# BW1092_TopLevel.net
KiCad netlist of a schematic drawn in Altium Designer
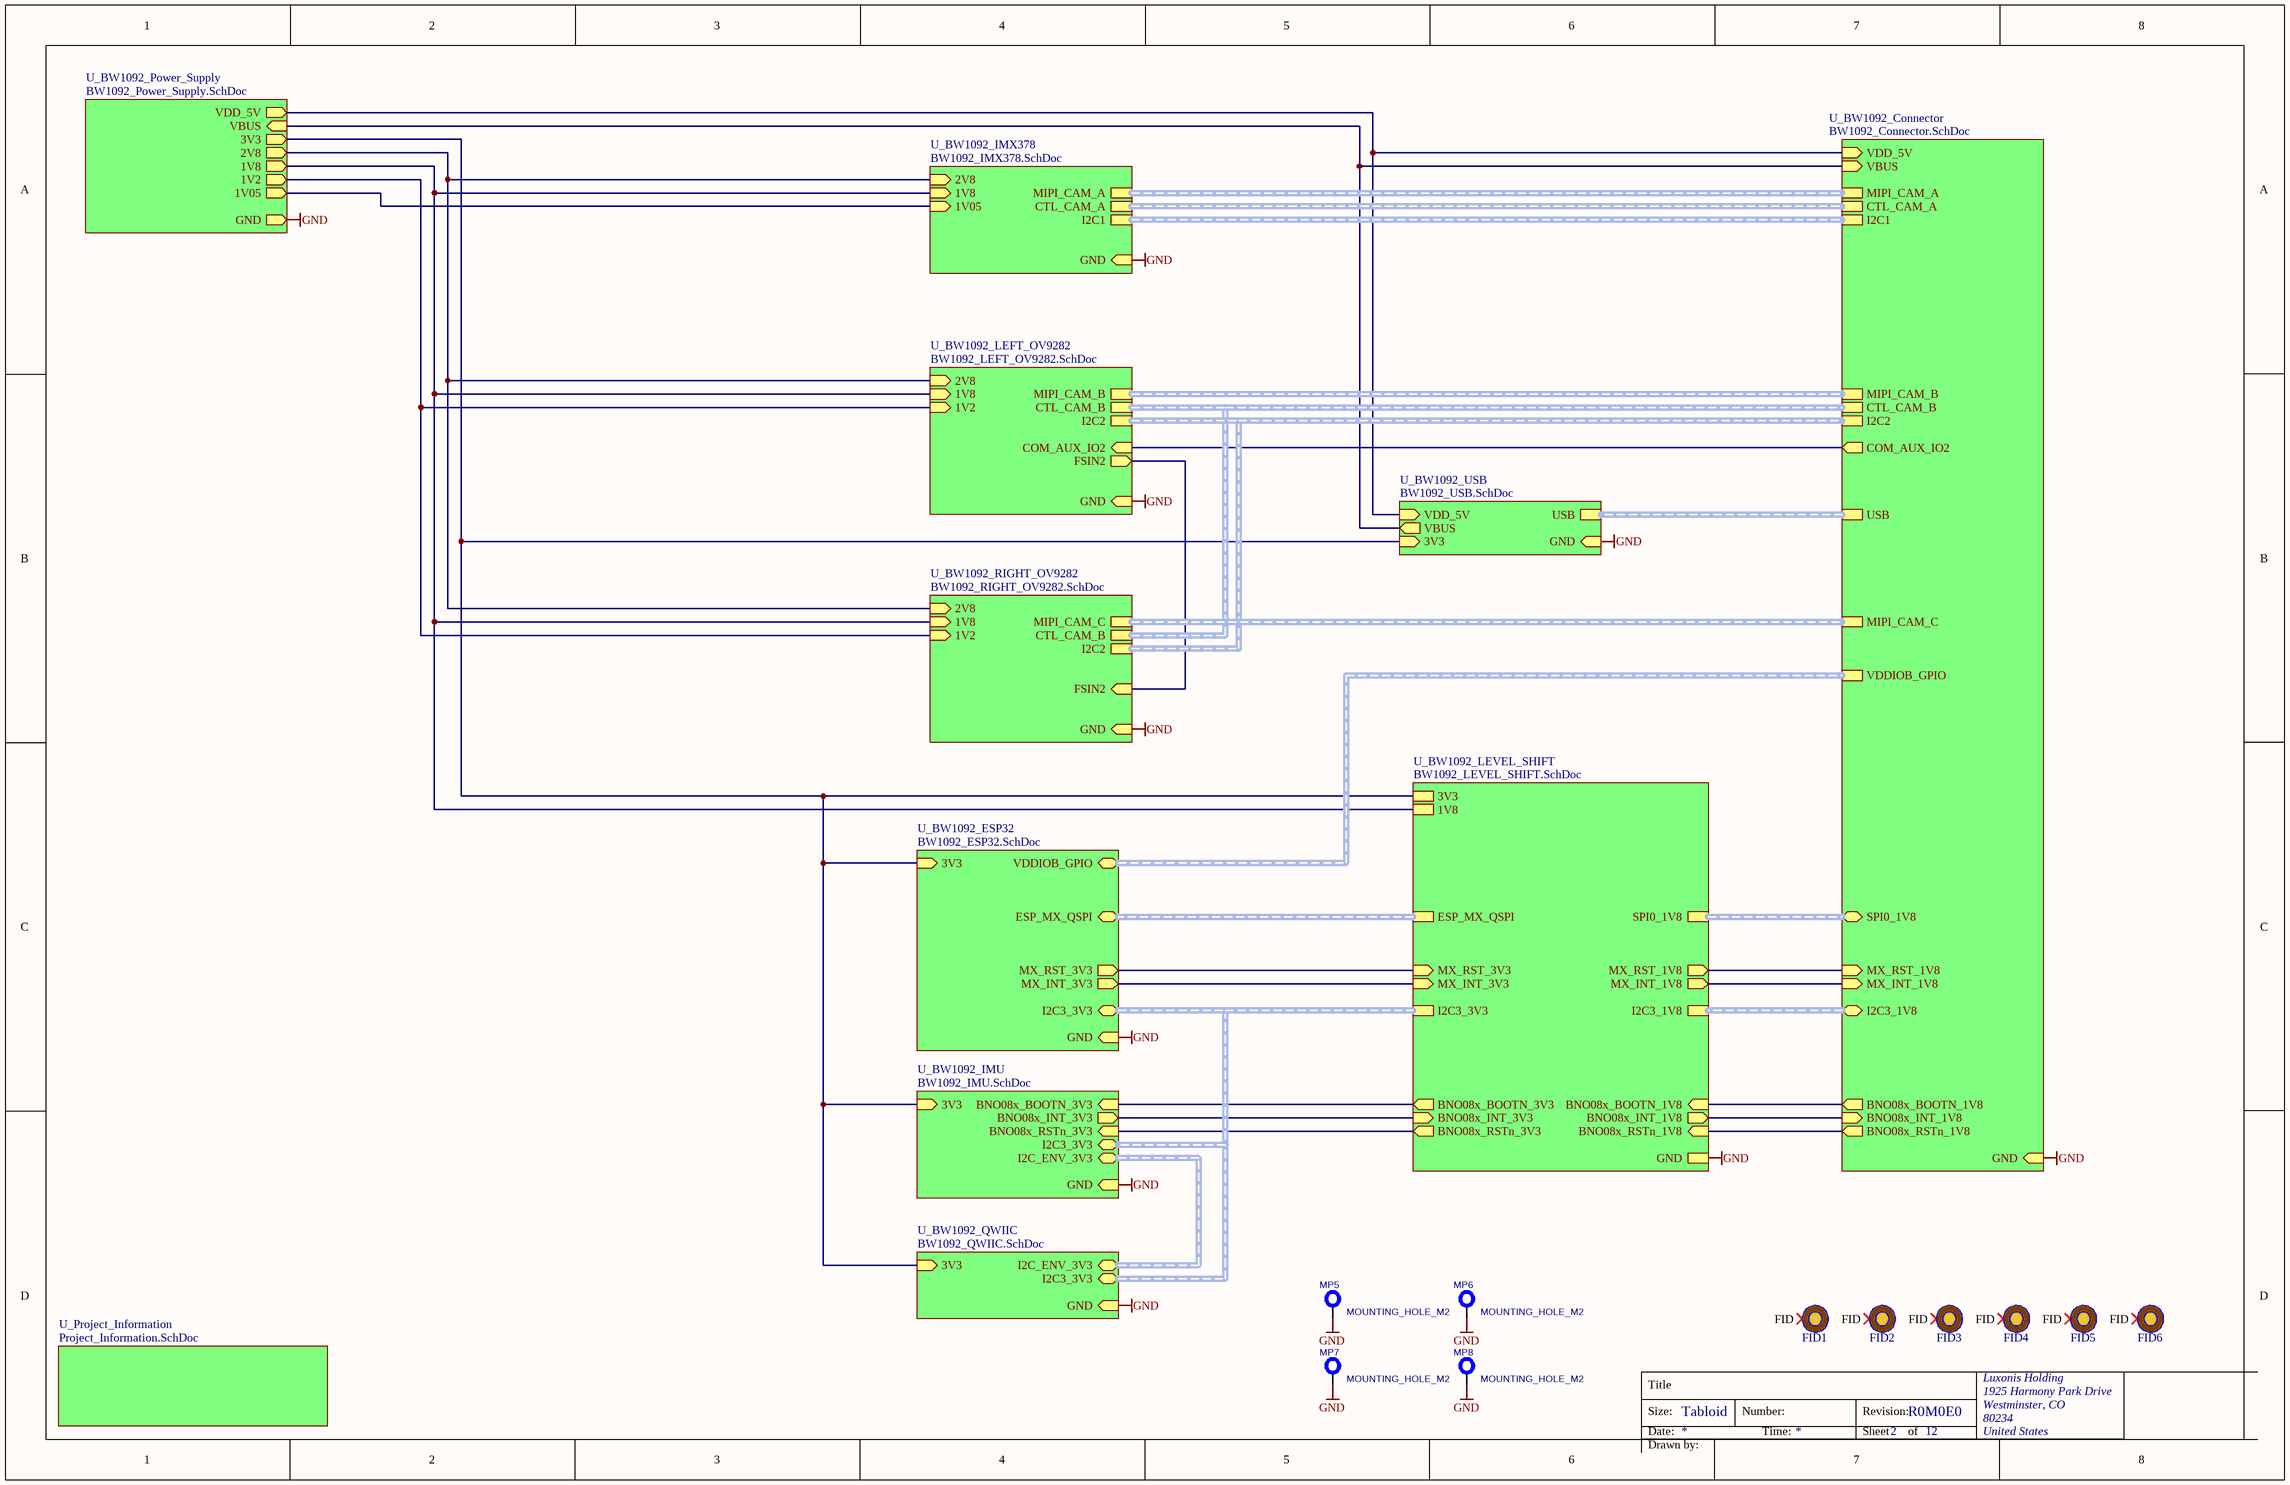
[diagram p0: BW1092_TopLevel.SchDoc]

(export (version "E")
  (design (tool "Eeschema 10.0.6"))
  (components
    (comp (ref "FID1")
      (value "FIDUCIAL_ROUND_1MM")
      (footprint "LuxonisMaster:FIDUCIAL_ROUND_1MM")
      (description "Fiducial with various available footprints")
      (libsource (lib "LuxonisMaster") (part "FIDUCIAL"))
    )
    (comp (ref "FID2")
      (value "FIDUCIAL_ROUND_1MM")
      (footprint "LuxonisMaster:FIDUCIAL_ROUND_1MM")
      (description "Fiducial with various available footprints")
      (libsource (lib "LuxonisMaster") (part "FIDUCIAL"))
    )
    (comp (ref "FID3")
      (value "FIDUCIAL_ROUND_1MM")
      (footprint "LuxonisMaster:FIDUCIAL_ROUND_1MM")
      (description "Fiducial with various available footprints")
      (libsource (lib "LuxonisMaster") (part "FIDUCIAL"))
    )
    (comp (ref "FID4")
      (value "FIDUCIAL_ROUND_1MM")
      (footprint "LuxonisMaster:FIDUCIAL_ROUND_1MM")
      (description "Fiducial with various available footprints")
      (libsource (lib "LuxonisMaster") (part "FIDUCIAL"))
    )
    (comp (ref "FID5")
      (value "FIDUCIAL_ROUND_1MM")
      (footprint "LuxonisMaster:FIDUCIAL_ROUND_1MM")
      (description "Fiducial with various available footprints")
      (libsource (lib "LuxonisMaster") (part "FIDUCIAL"))
    )
    (comp (ref "FID6")
      (value "FIDUCIAL_ROUND_1MM")
      (footprint "LuxonisMaster:FIDUCIAL_ROUND_1MM")
      (description "Fiducial with various available footprints")
      (libsource (lib "LuxonisMaster") (part "FIDUCIAL"))
    )
    (comp (ref "MP5")
      (value "MOUNTING_HOLE_M2")
      (footprint "LuxonisMaster:MOUNTING_HOLE_M2")
      (description "=CurrentFootprint")
      (libsource (lib "LuxonisMaster") (part "MP_Mounting-Holes"))
    )
    (comp (ref "MP6")
      (value "MOUNTING_HOLE_M2")
      (footprint "LuxonisMaster:MOUNTING_HOLE_M2")
      (description "=CurrentFootprint")
      (libsource (lib "LuxonisMaster") (part "MP_Mounting-Holes"))
    )
    (comp (ref "MP7")
      (value "MOUNTING_HOLE_M2")
      (footprint "LuxonisMaster:MOUNTING_HOLE_M2")
      (description "=CurrentFootprint")
      (libsource (lib "LuxonisMaster") (part "MP_Mounting-Holes"))
    )
    (comp (ref "MP8")
      (value "MOUNTING_HOLE_M2")
      (footprint "LuxonisMaster:MOUNTING_HOLE_M2")
      (description "=CurrentFootprint")
      (libsource (lib "LuxonisMaster") (part "MP_Mounting-Holes"))
    )
  )
  (nets
    (net (code "34") (name "GND") (class "Default")
      (node (ref "MP5") (pin "1") (pintype "passive"))
      (node (ref "MP6") (pin "1") (pintype "passive"))
      (node (ref "MP7") (pin "1") (pintype "passive"))
      (node (ref "MP8") (pin "1") (pintype "passive"))
    )
    (net (code "35") (name "unconnected-(FID1-PadFID)") (class "Default")
      (node (ref "FID1") (pin "FID") (pinfunction "FID_FID") (pintype "input+no_connect"))
    )
    (net (code "36") (name "unconnected-(FID2-PadFID)") (class "Default")
      (node (ref "FID2") (pin "FID") (pinfunction "FID_FID") (pintype "input+no_connect"))
    )
    (net (code "37") (name "unconnected-(FID3-PadFID)") (class "Default")
      (node (ref "FID3") (pin "FID") (pinfunction "FID_FID") (pintype "input+no_connect"))
    )
    (net (code "38") (name "unconnected-(FID4-PadFID)") (class "Default")
      (node (ref "FID4") (pin "FID") (pinfunction "FID_FID") (pintype "input+no_connect"))
    )
    (net (code "39") (name "unconnected-(FID5-PadFID)") (class "Default")
      (node (ref "FID5") (pin "FID") (pinfunction "FID_FID") (pintype "input+no_connect"))
    )
    (net (code "40") (name "unconnected-(FID6-PadFID)") (class "Default")
      (node (ref "FID6") (pin "FID") (pinfunction "FID_FID") (pintype "input+no_connect"))
    )
  )
)
